# AUGIS_Voltage_Regulator_Board.net
KiCad netlist of a schematic drawn in EasyEDA
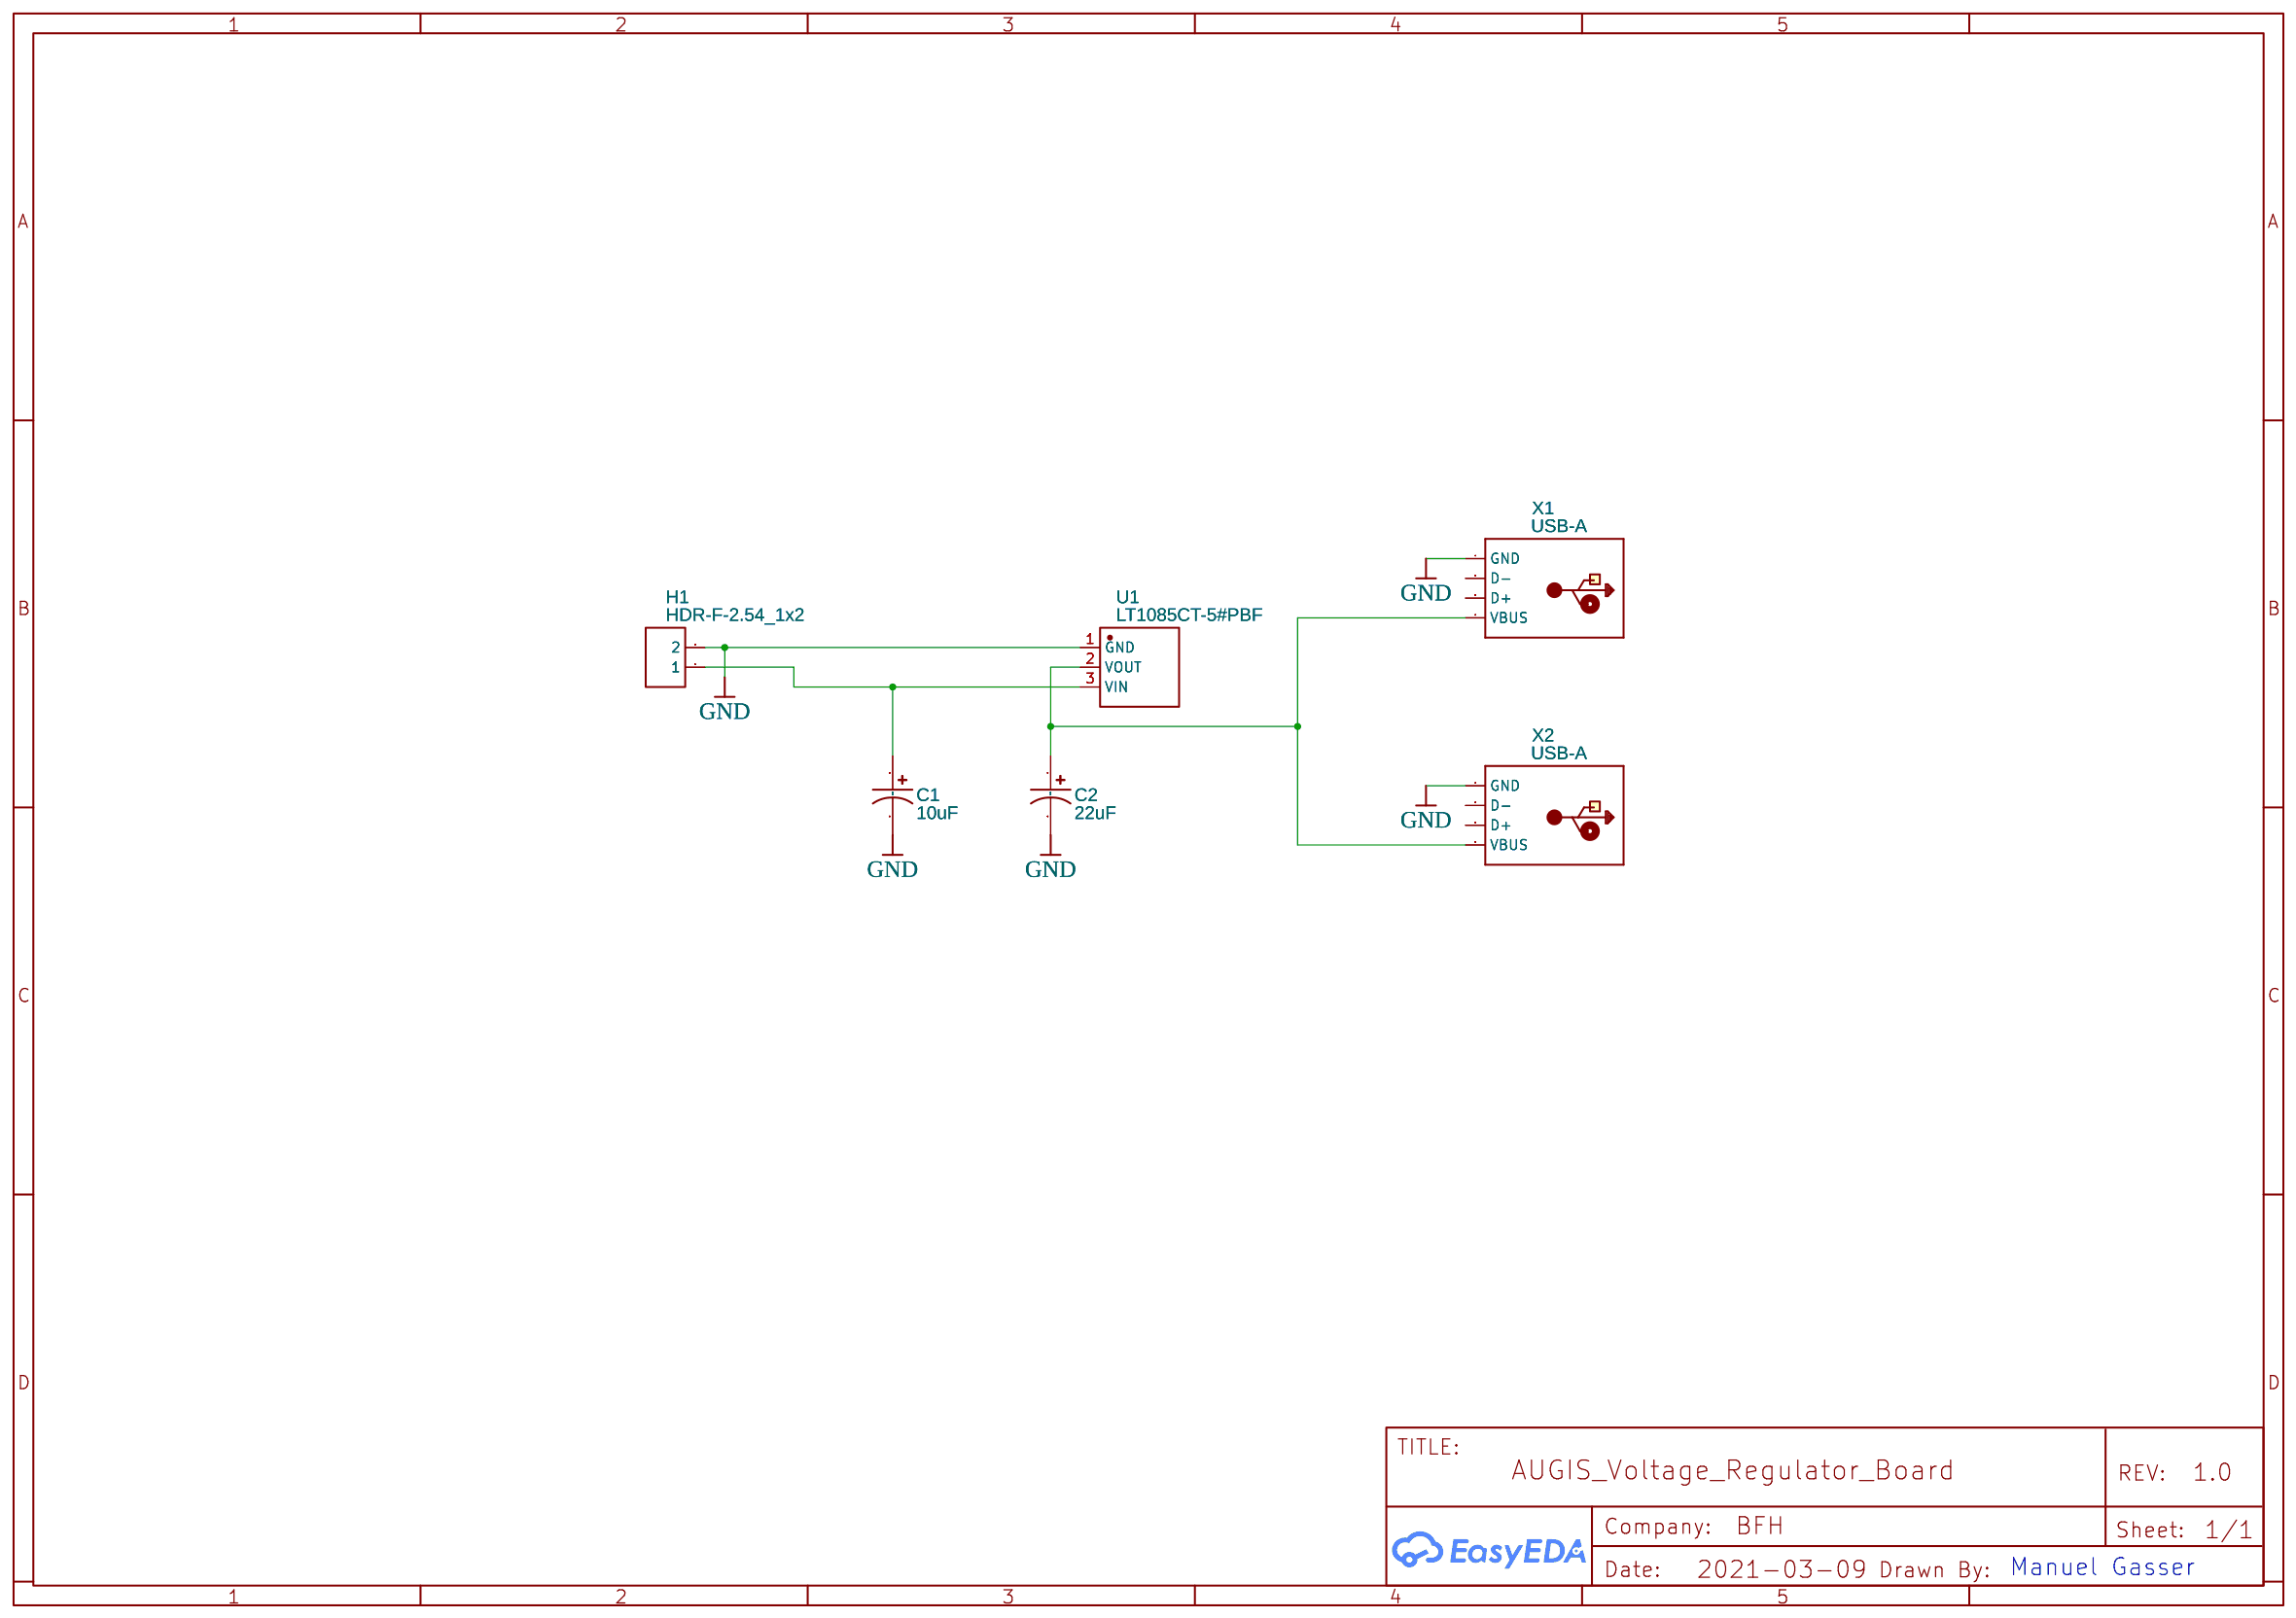
[diagram p0: schematic sheet]

(export (version "E")
  (design (tool "Eeschema 10.0.6"))
  (components
    (comp (ref "C1") (value "10uF") (libsource (lib "") (part "C_Tan_SMD_A_US")))
    (comp (ref "C2") (value "22uF") (libsource (lib "") (part "C_Tan_SMD_A_US")))
    (comp (ref "H1")
      (value "HDR-F-2.54_1x2")
      (fields (field (name "BOM_Supplier Part") "C49661"))
      (libsource (lib "") (part "HDR-F-2.54_1x2"))
    )
    (comp (ref "U1")
      (value "LT1085CT-5#PBF")
      (fields (field (name "BOM_Supplier Part") "C661212"))
      (libsource (lib "") (part "LT1085CT-5#PBF"))
    )
    (comp (ref "X1") (value "USB-A") (libsource (lib "") (part "USB-A")))
    (comp (ref "X2") (value "USB-A") (libsource (lib "") (part "USB-A")))
  )
  (nets
    (net (code "1") (name "GND") (class "Default")
      (node (ref "C1") (pin "2") (pinfunction "2_2") (pintype "unspecified"))
      (node (ref "C2") (pin "2") (pinfunction "2_2") (pintype "unspecified"))
      (node (ref "H1") (pin "2") (pinfunction "2_2") (pintype "input"))
      (node (ref "U1") (pin "1") (pinfunction "GND_1") (pintype "unspecified"))
      (node (ref "X1") (pin "4") (pinfunction "GND_4") (pintype "passive"))
      (node (ref "X2") (pin "4") (pinfunction "GND_4") (pintype "passive"))
    )
    (net (code "2") (name "Net-(U1-VIN)") (class "Default")
      (node (ref "C1") (pin "1") (pinfunction "1_1") (pintype "unspecified"))
      (node (ref "H1") (pin "1") (pinfunction "1_1") (pintype "input"))
      (node (ref "U1") (pin "3") (pinfunction "VIN_3") (pintype "unspecified"))
    )
    (net (code "3") (name "Net-(U1-VOUT)") (class "Default")
      (node (ref "C2") (pin "1") (pinfunction "1_1") (pintype "unspecified"))
      (node (ref "U1") (pin "2") (pinfunction "VOUT_2") (pintype "unspecified"))
      (node (ref "X1") (pin "1") (pinfunction "VBUS_1") (pintype "passive"))
      (node (ref "X2") (pin "1") (pinfunction "VBUS_1") (pintype "passive"))
    )
    (net (code "4") (name "unconnected-(X1-D+-Pad3)") (class "Default")
      (node (ref "X1") (pin "3") (pinfunction "D+_3") (pintype "unspecified"))
    )
    (net (code "5") (name "unconnected-(X1-D--Pad2)") (class "Default")
      (node (ref "X1") (pin "2") (pinfunction "D-_2") (pintype "unspecified"))
    )
    (net (code "6") (name "unconnected-(X2-D+-Pad3)") (class "Default")
      (node (ref "X2") (pin "3") (pinfunction "D+_3") (pintype "unspecified"))
    )
    (net (code "7") (name "unconnected-(X2-D--Pad2)") (class "Default")
      (node (ref "X2") (pin "2") (pinfunction "D-_2") (pintype "unspecified"))
    )
  )
)
